# usb.net
KiCad netlist of a schematic drawn in Altium Designer
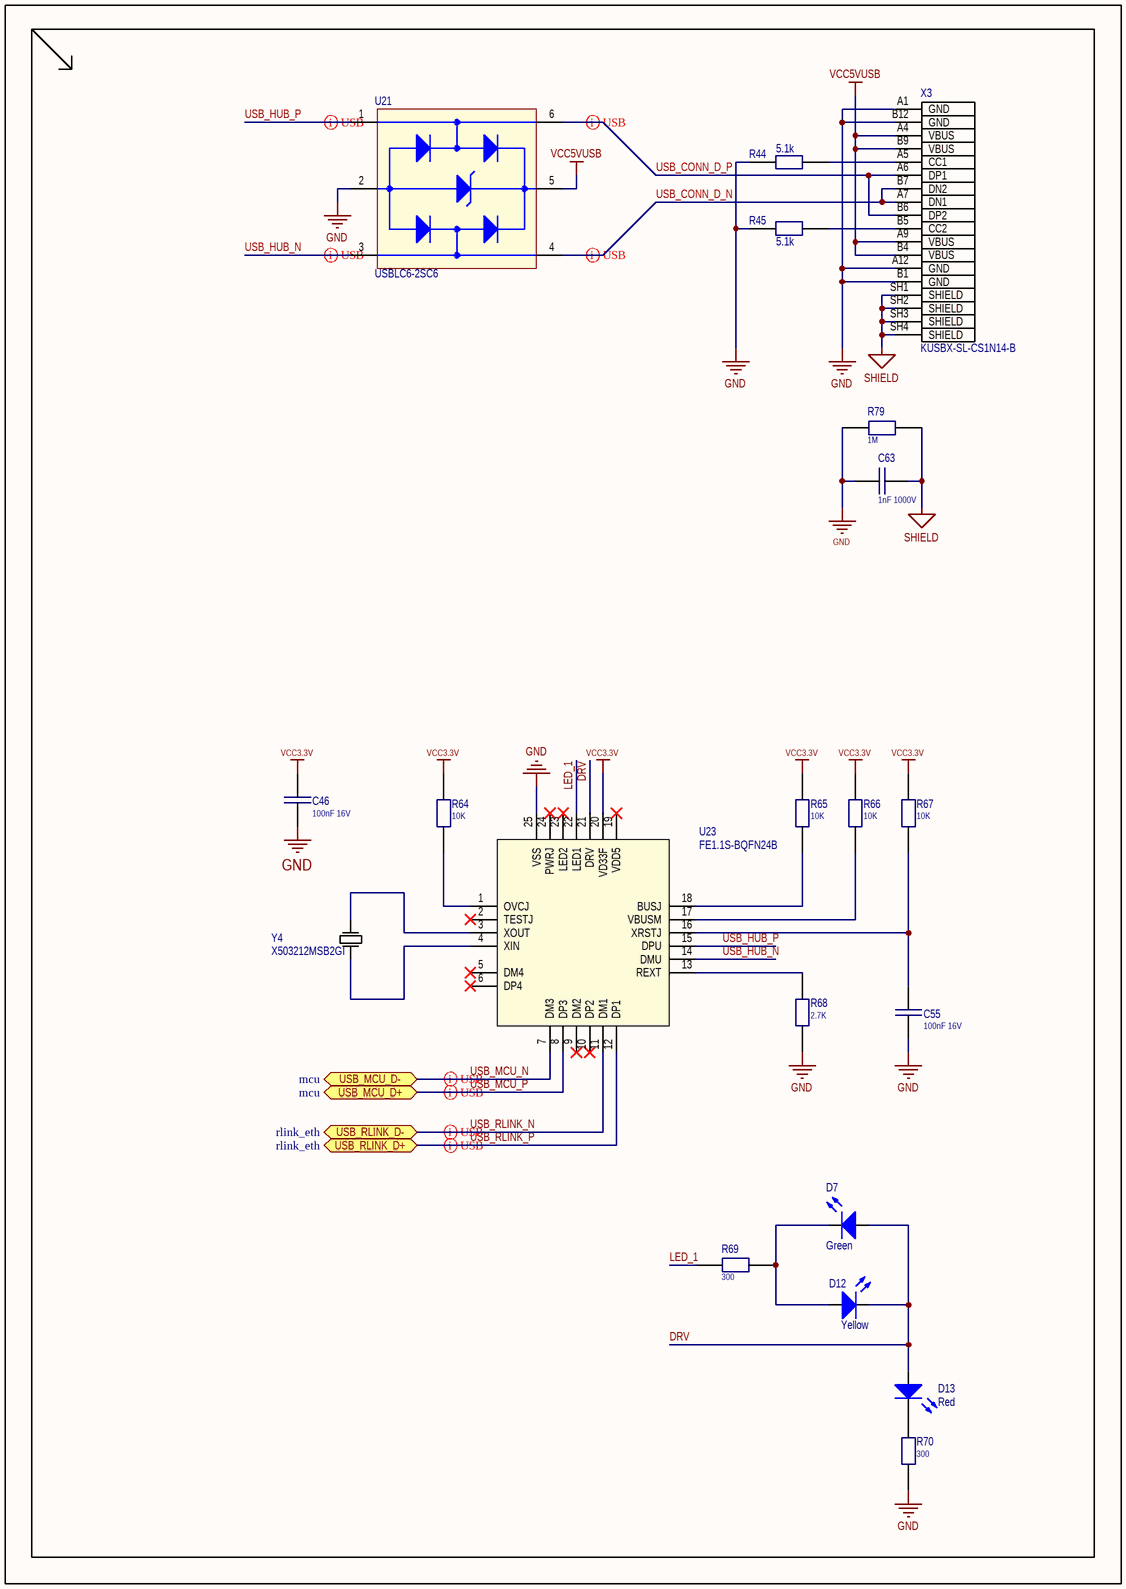
[diagram p0: usb.SchDoc]

(export (version "E")
  (design (tool "Eeschema 10.0.6"))
  (components
    (comp (ref "C46")
      (value "100nF 16V")
      (footprint "C_0402")
      (description "Capacitor")
      (fields (field (name "PART") "CC0402KRX7R7BB104") (field (name "ALTERNATIVE PART") "CC0402KRX5R7BB104"))
      (libsource (lib "capacitors") (part "C0402"))
    )
    (comp (ref "C55")
      (value "100nF 16V")
      (footprint "C_0402")
      (description "Capacitor")
      (fields (field (name "PART") "CC0402KRX7R7BB104") (field (name "ALTERNATIVE PART") "CC0402KRX5R7BB104"))
      (libsource (lib "capacitors") (part "C0402"))
    )
    (comp (ref "C63")
      (value "1nF 1000V")
      (footprint "C_1206")
      (description "Capacitor")
      (fields (field (name "PART") "CC1206KKX7RCBB102") (field (name "ALTERNATIVE PART") "CL31B102KIFNNNE"))
      (libsource (lib "capacitors") (part "C1206"))
    )
    (comp (ref "D7")
      (value "Green")
      (footprint "LED_0603")
      (description "LED")
      (fields (field (name "PART") "FYLS-0603PGC") (field (name "ALTERNATIVE PART") "KP-1608CGCK"))
      (libsource (lib "led_lcd") (part "LED_SMT_0603"))
    )
    (comp (ref "D12")
      (value "Yellow")
      (footprint "LED_0603")
      (description "LED")
      (fields (field (name "PART") "FYLS-0603PGC") (field (name "ALTERNATIVE PART") "KP-1608CGCK"))
      (libsource (lib "led_lcd") (part "LED_SMT_0603"))
    )
    (comp (ref "D13")
      (value "Red")
      (footprint "LED_0603")
      (description "LED")
      (fields (field (name "PART") "FYLS-0603PGC") (field (name "ALTERNATIVE PART") "KP-1608CGCK"))
      (libsource (lib "led_lcd") (part "LED_SMT_0603"))
    )
    (comp (ref "R44")
      (value "5.1k")
      (footprint "R_0603")
      (description "Resistor")
      (fields (field (name "PART") "RC0603JR-075K1L") (field (name "JLCPCB PART") "C14677"))
      (libsource (lib "resistors") (part "RES_SMD"))
    )
    (comp (ref "R45")
      (value "5.1k")
      (footprint "R_0603")
      (description "Resistor")
      (fields (field (name "PART") "RC0603JR-075K1L") (field (name "JLCPCB PART") "C14677"))
      (libsource (lib "resistors") (part "RES_SMD"))
    )
    (comp (ref "R64")
      (value "10K")
      (footprint "R_0402")
      (description "Resistor")
      (fields (field (name "PART") "RC0402JR-0710KL") (field (name "JLCPCB PART") "C60489"))
      (libsource (lib "resistors") (part "R0402"))
    )
    (comp (ref "R65")
      (value "10K")
      (footprint "R_0402")
      (description "Resistor")
      (fields (field (name "PART") "RC0402JR-0710KL") (field (name "JLCPCB PART") "C60489"))
      (libsource (lib "resistors") (part "R0402"))
    )
    (comp (ref "R66")
      (value "10K")
      (footprint "R_0402")
      (description "Resistor")
      (fields (field (name "PART") "RC0402JR-0710KL") (field (name "JLCPCB PART") "C60489"))
      (libsource (lib "resistors") (part "R0402"))
    )
    (comp (ref "R67")
      (value "10K")
      (footprint "R_0402")
      (description "Resistor")
      (fields (field (name "PART") "RC0402JR-0710KL") (field (name "JLCPCB PART") "C60489"))
      (libsource (lib "resistors") (part "R0402"))
    )
    (comp (ref "R68")
      (value "2.7K")
      (footprint "R_0402")
      (description "Resistor")
      (fields (field (name "PART") "RC0402FR-072K7L") (field (name "JLCPCB PART") "C138017"))
      (libsource (lib "resistors") (part "R0402"))
    )
    (comp (ref "R69")
      (value "300")
      (footprint "R_0603")
      (description "Resistor")
      (fields (field (name "PART") "RC0603FR-07300RL") (field (name "JLCPCB PART") "C114617"))
      (libsource (lib "resistors") (part "R0603"))
    )
    (comp (ref "R70")
      (value "300")
      (footprint "R_0603")
      (description "Resistor")
      (fields (field (name "PART") "RC0603FR-07300RL") (field (name "JLCPCB PART") "C114617"))
      (libsource (lib "resistors") (part "R0603"))
    )
    (comp (ref "R79")
      (value "1M")
      (footprint "R_1206")
      (description "Resistor")
      (fields (field (name "PART") "RC1206FR-071ML") (field (name "JLCPCB PART") "C108083"))
      (libsource (lib "resistors") (part "R1206"))
    )
    (comp (ref "U21")
      (value "USBLC6-2SC6")
      (footprint "diode:SOT95P280X145-6N")
      (description "17V Clamp 5A (8/20Âµs) Ipp Tvs Diode Surface Mount SOT-23-6")
      (fields (field (name "MF") "STMicroelectronics") (field (name "JLCPCB PART") "C2827654"))
      (libsource (lib "diode") (part "USBLC6-2SC6"))
    )
    (comp (ref "U23")
      (value "FE1.1S-BQFN24B")
      (footprint "QFN50P400X400X80-25N-D")
      (description "USB 2.0 HIGH SPEED 4-PORT HUB CONTROLLER")
      (fields (field (name "JLCPCB PART") "C6776948"))
      (libsource (lib "discret_ic") (part "FE1.1S-BQFN24B"))
    )
    (comp (ref "X3")
      (value "KUSBX-SL-CS1N14-B")
      (footprint "MOLEX_2169890001")
      (description "USB Connector USB TYPE C UPRIGHT STRAIGHT TAB 14 PIN")
      (fields (field (name "JLCPCB PART") "C2894906"))
      (libsource (lib "connectors_socets") (part "MOLEX_216989-0001"))
    )
    (comp (ref "Y4")
      (value "X503212MSB2GI")
      (footprint "X5032")
      (description "Crystal Oscillator")
      (fields (field (name "JLCPCB PART") "C112573"))
      (libsource (lib "crystals_oscillators") (part "X503212MSB2GI"))
    )
  )
  (nets
    (net (code "1") (name "/DRV") (class "Default")
      (node (ref "D12") (pin "2") (pinfunction "K_2") (pintype "passive"))
      (node (ref "D13") (pin "1") (pinfunction "A_1") (pintype "passive"))
      (node (ref "D7") (pin "1") (pinfunction "A_1") (pintype "passive"))
      (node (ref "U23") (pin "21") (pinfunction "DRV_21") (pintype "passive"))
    )
    (net (code "2") (name "/LED_1") (class "Default")
      (node (ref "R69") (pin "2") (pinfunction "2_2") (pintype "passive"))
      (node (ref "U23") (pin "22") (pinfunction "LED1_22") (pintype "passive"))
    )
    (net (code "3") (name "/USB_CONN_D_N") (class "Default")
      (node (ref "U21") (pin "4") (pinfunction "I/O2_OUT_4") (pintype "passive"))
      (node (ref "X3") (pin "A7") (pinfunction "DN1_A7") (pintype "passive"))
      (node (ref "X3") (pin "B7") (pinfunction "DN2_B7") (pintype "passive"))
    )
    (net (code "4") (name "/USB_CONN_D_P") (class "Default")
      (node (ref "U21") (pin "6") (pinfunction "I/O1_OUT_6") (pintype "passive"))
      (node (ref "X3") (pin "A6") (pinfunction "DP1_A6") (pintype "passive"))
      (node (ref "X3") (pin "B6") (pinfunction "DP2_B6") (pintype "passive"))
    )
    (net (code "5") (name "/USB_HUB_N") (class "Default")
      (node (ref "U21") (pin "3") (pinfunction "I/O2_IN_3") (pintype "passive"))
      (node (ref "U23") (pin "14") (pinfunction "DMU_14") (pintype "passive"))
    )
    (net (code "6") (name "/USB_HUB_P") (class "Default")
      (node (ref "U21") (pin "1") (pinfunction "I/O1_IN_1") (pintype "passive"))
      (node (ref "U23") (pin "15") (pinfunction "DPU_15") (pintype "passive"))
    )
    (net (code "7") (name "/USB_MCU_N") (class "Default")
      (node (ref "U23") (pin "7") (pinfunction "DM3_7") (pintype "passive"))
    )
    (net (code "8") (name "/USB_MCU_P") (class "Default")
      (node (ref "U23") (pin "8") (pinfunction "DP3_8") (pintype "passive"))
    )
    (net (code "9") (name "/USB_RLINK_N") (class "Default")
      (node (ref "U23") (pin "11") (pinfunction "DM1_11") (pintype "passive"))
    )
    (net (code "10") (name "/USB_RLINK_P") (class "Default")
      (node (ref "U23") (pin "12") (pinfunction "DP1_12") (pintype "passive"))
    )
    (net (code "11") (name "GND") (class "Default")
      (node (ref "C46") (pin "1") (pinfunction "1_1") (pintype "passive"))
      (node (ref "C55") (pin "2") (pinfunction "2_2") (pintype "passive"))
      (node (ref "C63") (pin "1") (pinfunction "1_1") (pintype "passive"))
      (node (ref "R44") (pin "1") (pinfunction "1_1") (pintype "passive"))
      (node (ref "R45") (pin "1") (pinfunction "1_1") (pintype "passive"))
      (node (ref "R68") (pin "2") (pinfunction "2_2") (pintype "passive"))
      (node (ref "R70") (pin "1") (pinfunction "1_1") (pintype "passive"))
      (node (ref "R79") (pin "1") (pinfunction "1_1") (pintype "passive"))
      (node (ref "U21") (pin "2") (pinfunction "GND_2") (pintype "passive"))
      (node (ref "U23") (pin "25") (pinfunction "VSS_25") (pintype "power_in"))
      (node (ref "X3") (pin "A1") (pinfunction "GND_A1") (pintype "passive"))
      (node (ref "X3") (pin "A12") (pinfunction "GND_A12") (pintype "passive"))
      (node (ref "X3") (pin "B1") (pinfunction "GND_B1") (pintype "passive"))
      (node (ref "X3") (pin "B12") (pinfunction "GND_B12") (pintype "passive"))
    )
    (net (code "12") (name "Net-(D12-A)") (class "Default")
      (node (ref "D12") (pin "1") (pinfunction "A_1") (pintype "passive"))
      (node (ref "D7") (pin "2") (pinfunction "K_2") (pintype "passive"))
      (node (ref "R69") (pin "1") (pinfunction "1_1") (pintype "passive"))
    )
    (net (code "13") (name "Net-(D13-K)") (class "Default")
      (node (ref "D13") (pin "2") (pinfunction "K_2") (pintype "passive"))
      (node (ref "R70") (pin "2") (pinfunction "2_2") (pintype "passive"))
    )
    (net (code "14") (name "Net-(U23-BUSJ)") (class "Default")
      (node (ref "R65") (pin "1") (pinfunction "1_1") (pintype "passive"))
      (node (ref "U23") (pin "18") (pinfunction "BUSJ_18") (pintype "passive"))
    )
    (net (code "15") (name "Net-(U23-OVCJ)") (class "Default")
      (node (ref "R64") (pin "1") (pinfunction "1_1") (pintype "passive"))
      (node (ref "U23") (pin "1") (pinfunction "OVCJ_1") (pintype "passive"))
    )
    (net (code "16") (name "Net-(U23-REXT)") (class "Default")
      (node (ref "R68") (pin "1") (pinfunction "1_1") (pintype "passive"))
      (node (ref "U23") (pin "13") (pinfunction "REXT_13") (pintype "passive"))
    )
    (net (code "17") (name "Net-(U23-VBUSM)") (class "Default")
      (node (ref "R66") (pin "1") (pinfunction "1_1") (pintype "passive"))
      (node (ref "U23") (pin "17") (pinfunction "VBUSM_17") (pintype "passive"))
    )
    (net (code "18") (name "Net-(U23-XIN)") (class "Default")
      (node (ref "U23") (pin "4") (pinfunction "XIN_4") (pintype "passive"))
      (node (ref "Y4") (pin "2") (pinfunction "2_2") (pintype "passive"))
    )
    (net (code "19") (name "Net-(U23-XOUT)") (class "Default")
      (node (ref "U23") (pin "3") (pinfunction "XOUT_3") (pintype "passive"))
      (node (ref "Y4") (pin "1") (pinfunction "1_1") (pintype "passive"))
    )
    (net (code "20") (name "Net-(U23-XRSTJ)") (class "Default")
      (node (ref "C55") (pin "1") (pinfunction "1_1") (pintype "passive"))
      (node (ref "R67") (pin "1") (pinfunction "1_1") (pintype "passive"))
      (node (ref "U23") (pin "16") (pinfunction "XRSTJ_16") (pintype "passive"))
    )
    (net (code "21") (name "Net-(X3-CC1)") (class "Default")
      (node (ref "R44") (pin "2") (pinfunction "2_2") (pintype "passive"))
      (node (ref "X3") (pin "A5") (pinfunction "CC1_A5") (pintype "passive"))
    )
    (net (code "22") (name "Net-(X3-CC2)") (class "Default")
      (node (ref "R45") (pin "2") (pinfunction "2_2") (pintype "passive"))
      (node (ref "X3") (pin "B5") (pinfunction "CC2_B5") (pintype "passive"))
    )
    (net (code "23") (name "SHIELD") (class "Default")
      (node (ref "C63") (pin "2") (pinfunction "2_2") (pintype "passive"))
      (node (ref "R79") (pin "2") (pinfunction "2_2") (pintype "passive"))
      (node (ref "X3") (pin "SH1") (pinfunction "SHIELD_SH1") (pintype "passive"))
      (node (ref "X3") (pin "SH2") (pinfunction "SHIELD_SH2") (pintype "passive"))
      (node (ref "X3") (pin "SH3") (pinfunction "SHIELD_SH3") (pintype "passive"))
      (node (ref "X3") (pin "SH4") (pinfunction "SHIELD_SH4") (pintype "passive"))
    )
    (net (code "24") (name "VCC3.3V") (class "Default")
      (node (ref "C46") (pin "2") (pinfunction "2_2") (pintype "passive"))
      (node (ref "R64") (pin "2") (pinfunction "2_2") (pintype "passive"))
      (node (ref "R65") (pin "2") (pinfunction "2_2") (pintype "passive"))
      (node (ref "R66") (pin "2") (pinfunction "2_2") (pintype "passive"))
      (node (ref "R67") (pin "2") (pinfunction "2_2") (pintype "passive"))
      (node (ref "U23") (pin "20") (pinfunction "VD33F_20") (pintype "power_in"))
    )
    (net (code "25") (name "VCC5VUSB") (class "Default")
      (node (ref "U21") (pin "5") (pinfunction "VBUS_5") (pintype "passive"))
      (node (ref "X3") (pin "A4") (pinfunction "VBUS_A4") (pintype "passive"))
      (node (ref "X3") (pin "A9") (pinfunction "VBUS_A9") (pintype "passive"))
      (node (ref "X3") (pin "B4") (pinfunction "VBUS_B4") (pintype "passive"))
      (node (ref "X3") (pin "B9") (pinfunction "VBUS_B9") (pintype "passive"))
    )
    (net (code "26") (name "unconnected-(U23-DM2-Pad9)") (class "Default")
      (node (ref "U23") (pin "9") (pinfunction "DM2_9") (pintype "passive+no_connect"))
    )
    (net (code "27") (name "unconnected-(U23-DM4-Pad5)") (class "Default")
      (node (ref "U23") (pin "5") (pinfunction "DM4_5") (pintype "passive+no_connect"))
    )
    (net (code "28") (name "unconnected-(U23-DP2-Pad10)") (class "Default")
      (node (ref "U23") (pin "10") (pinfunction "DP2_10") (pintype "passive+no_connect"))
    )
    (net (code "29") (name "unconnected-(U23-DP4-Pad6)") (class "Default")
      (node (ref "U23") (pin "6") (pinfunction "DP4_6") (pintype "passive+no_connect"))
    )
    (net (code "30") (name "unconnected-(U23-LED2-Pad23)") (class "Default")
      (node (ref "U23") (pin "23") (pinfunction "LED2_23") (pintype "passive+no_connect"))
    )
    (net (code "31") (name "unconnected-(U23-PWRJ-Pad24)") (class "Default")
      (node (ref "U23") (pin "24") (pinfunction "PWRJ_24") (pintype "passive+no_connect"))
    )
    (net (code "32") (name "unconnected-(U23-TESTJ-Pad2)") (class "Default")
      (node (ref "U23") (pin "2") (pinfunction "TESTJ_2") (pintype "passive+no_connect"))
    )
    (net (code "33") (name "unconnected-(U23-VDD5-Pad19)") (class "Default")
      (node (ref "U23") (pin "19") (pinfunction "VDD5_19") (pintype "power_in+no_connect"))
    )
  )
)
